# IoTSensorSchematic.net
KiCad netlist of a schematic drawn in EAGLE
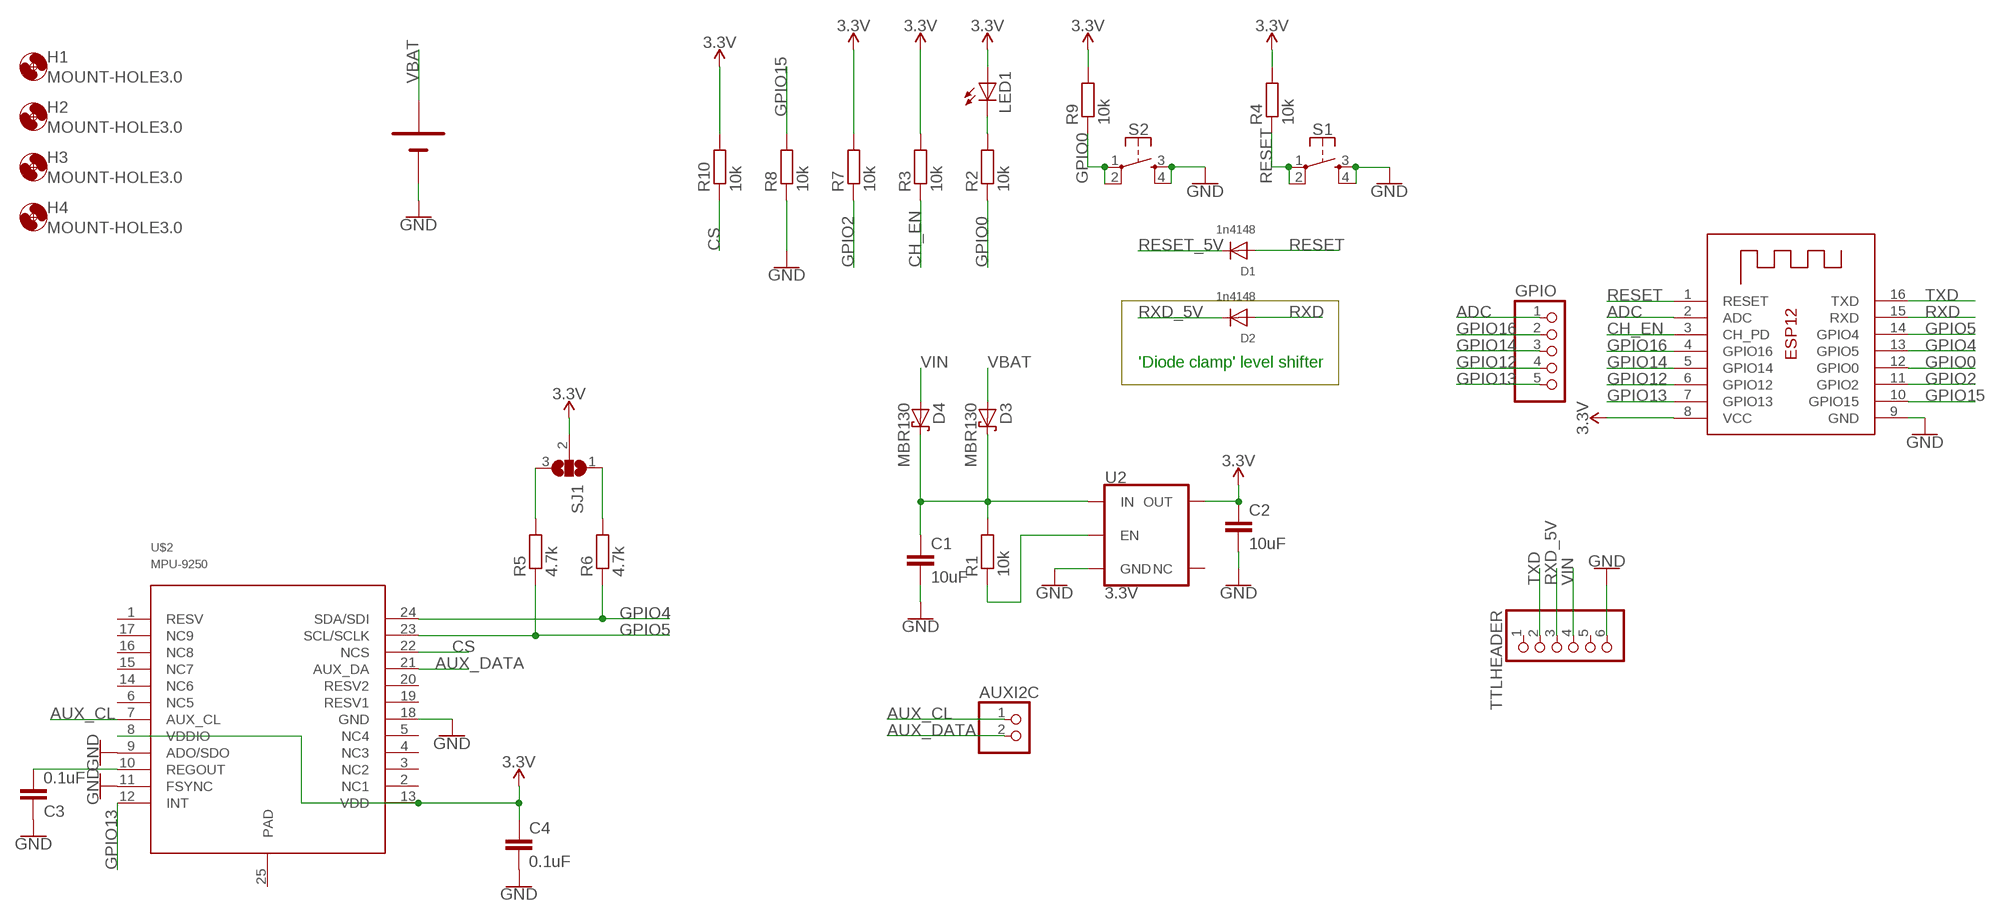
[diagram p0: schematic, sheet 1]

(export (version "E")
  (design (tool "Eeschema 10.0.6"))
  (components
    (comp (ref "AUXI2C")
      (value "PINHD-1X2")
      (footprint "eagle-import:1X02")
      (libsource (lib "eagle-import") (part "PINHD-1X2"))
    )
    (comp (ref "C1")
      (value "10uF")
      (footprint "eagle-import:C0805")
      (libsource (lib "eagle-import") (part "C-EUC0805"))
    )
    (comp (ref "C2")
      (value "10uF")
      (footprint "eagle-import:C0805")
      (libsource (lib "eagle-import") (part "C-EUC0805"))
    )
    (comp (ref "C3")
      (value "0.1uF")
      (footprint "eagle-import:C0805")
      (libsource (lib "eagle-import") (part "C-EUC0805"))
    )
    (comp (ref "C4")
      (value "0.1uF")
      (footprint "eagle-import:C0805")
      (libsource (lib "eagle-import") (part "C-EUC0805"))
    )
    (comp (ref "D1")
      (value "1n4148")
      (footprint "eagle-import:SMADIODE")
      (libsource (lib "eagle-import") (part "DIODESMA"))
    )
    (comp (ref "D2")
      (value "1n4148")
      (footprint "eagle-import:SMADIODE")
      (libsource (lib "eagle-import") (part "DIODESMA"))
    )
    (comp (ref "D3")
      (value "MBR130")
      (footprint "eagle-import:SMB")
      (libsource (lib "eagle-import") (part "MBRS130LT3"))
    )
    (comp (ref "D4")
      (value "MBR130")
      (footprint "eagle-import:SMB")
      (libsource (lib "eagle-import") (part "MBRS130LT3"))
    )
    (comp (ref "GPIO")
      (value "PINHD-1X5")
      (footprint "eagle-import:1X05")
      (libsource (lib "eagle-import") (part "PINHD-1X5"))
    )
    (comp (ref "H1")
      (value "MOUNT-HOLE3.0")
      (footprint "eagle-import:3,0")
      (libsource (lib "eagle-import") (part "MOUNT-HOLE3.0"))
    )
    (comp (ref "H2")
      (value "MOUNT-HOLE3.0")
      (footprint "eagle-import:3,0")
      (libsource (lib "eagle-import") (part "MOUNT-HOLE3.0"))
    )
    (comp (ref "H3")
      (value "MOUNT-HOLE3.0")
      (footprint "eagle-import:3,0")
      (libsource (lib "eagle-import") (part "MOUNT-HOLE3.0"))
    )
    (comp (ref "H4")
      (value "MOUNT-HOLE3.0")
      (footprint "eagle-import:3,0")
      (libsource (lib "eagle-import") (part "MOUNT-HOLE3.0"))
    )
    (comp (ref "LED1")
      (value "LEDCHIP-LED0805")
      (footprint "eagle-import:CHIP-LED0805")
      (libsource (lib "eagle-import") (part "LEDCHIP-LED0805"))
    )
    (comp (ref "R1")
      (value "10k")
      (footprint "eagle-import:R0805")
      (libsource (lib "eagle-import") (part "R-EU_R0805"))
    )
    (comp (ref "R2")
      (value "10k")
      (footprint "eagle-import:R0805")
      (libsource (lib "eagle-import") (part "R-EU_R0805"))
    )
    (comp (ref "R3")
      (value "10k")
      (footprint "eagle-import:R0805")
      (libsource (lib "eagle-import") (part "R-EU_R0805"))
    )
    (comp (ref "R4")
      (value "10k")
      (footprint "eagle-import:R0805")
      (libsource (lib "eagle-import") (part "R-EU_R0805"))
    )
    (comp (ref "R5")
      (value "4.7k")
      (footprint "eagle-import:R0805")
      (libsource (lib "eagle-import") (part "R-EU_R0805"))
    )
    (comp (ref "R6")
      (value "4.7k")
      (footprint "eagle-import:R0805")
      (libsource (lib "eagle-import") (part "R-EU_R0805"))
    )
    (comp (ref "R7")
      (value "10k")
      (footprint "eagle-import:R0805")
      (libsource (lib "eagle-import") (part "R-EU_R0805"))
    )
    (comp (ref "R8")
      (value "10k")
      (footprint "eagle-import:R0805")
      (libsource (lib "eagle-import") (part "R-EU_R0805"))
    )
    (comp (ref "R9")
      (value "10k")
      (footprint "eagle-import:R0805")
      (libsource (lib "eagle-import") (part "R-EU_R0805"))
    )
    (comp (ref "R10")
      (value "10k")
      (footprint "eagle-import:R0805")
      (libsource (lib "eagle-import") (part "R-EU_R0805"))
    )
    (comp (ref "S1")
      (value "MOMENTARY-SWITCH-SPST-2-SMD-5.2MM")
      (footprint "eagle-import:TACTILE_SWITCH_SMD_5.2MM")
      (libsource (lib "eagle-import") (part "MOMENTARY-SWITCH-SPST-2-SMD-5.2MM"))
    )
    (comp (ref "S2")
      (value "MOMENTARY-SWITCH-SPST-2-SMD-5.2MM")
      (footprint "eagle-import:TACTILE_SWITCH_SMD_5.2MM")
      (libsource (lib "eagle-import") (part "MOMENTARY-SWITCH-SPST-2-SMD-5.2MM"))
    )
    (comp (ref "SJ1")
      (value "SJ2W")
      (footprint "eagle-import:SJ_2")
      (libsource (lib "eagle-import") (part "SJ2W"))
    )
    (comp (ref "TTLHEADER")
      (value "PINHD-1X6")
      (footprint "eagle-import:1X06")
      (libsource (lib "eagle-import") (part "PINHD-1X6"))
    )
    (comp (ref "U$1")
      (value "SMTU_2450N")
      (footprint "eagle-import:SMTU_2450N")
      (libsource (lib "eagle-import") (part "SMTU_2450N"))
    )
    (comp (ref "U$2")
      (value "MPU-9250")
      (footprint "eagle-import:LEAD-QFN24")
      (libsource (lib "eagle-import") (part "MPU-9250"))
    )
    (comp (ref "U2")
      (value "3.3V")
      (footprint "eagle-import:SOT23-5")
      (libsource (lib "eagle-import") (part "V_REG_AP2112K-3.3V"))
    )
    (comp (ref "X1")
      (value "ESP-12")
      (footprint "eagle-import:ESP-12")
      (libsource (lib "eagle-import") (part "ESP-12"))
    )
  )
  (nets
    (net (code "1") (name "/ADC") (class "Default")
      (node (ref "GPIO") (pin "1") (pinfunction "1_1") (pintype "passive"))
      (node (ref "X1") (pin "2") (pinfunction "ADC_2") (pintype "passive"))
    )
    (net (code "2") (name "/AUX_CL") (class "Default")
      (node (ref "AUXI2C") (pin "1") (pinfunction "1_1") (pintype "passive"))
      (node (ref "U$2") (pin "7") (pinfunction "AUX_CL_7") (pintype "bidirectional"))
    )
    (net (code "3") (name "/AUX_DATA") (class "Default")
      (node (ref "AUXI2C") (pin "2") (pinfunction "2_2") (pintype "passive"))
      (node (ref "U$2") (pin "21") (pinfunction "AUX_DA_21") (pintype "bidirectional"))
    )
    (net (code "4") (name "/CH_EN") (class "Default")
      (node (ref "R3") (pin "1") (pinfunction "1_1") (pintype "passive"))
      (node (ref "X1") (pin "3") (pinfunction "CH_PD_3") (pintype "input"))
    )
    (net (code "5") (name "/CS") (class "Default")
      (node (ref "R10") (pin "1") (pinfunction "1_1") (pintype "passive"))
      (node (ref "U$2") (pin "22") (pinfunction "NCS_22") (pintype "bidirectional"))
    )
    (net (code "6") (name "/GPIO0") (class "Default")
      (node (ref "R2") (pin "1") (pinfunction "1_1") (pintype "passive"))
      (node (ref "R9") (pin "1") (pinfunction "1_1") (pintype "passive"))
      (node (ref "S2") (pin "1") (pinfunction "1_1") (pintype "passive"))
      (node (ref "S2") (pin "2") (pinfunction "2_2") (pintype "passive"))
      (node (ref "X1") (pin "12") (pinfunction "GPIO0_12") (pintype "bidirectional"))
    )
    (net (code "7") (name "/GPIO2") (class "Default")
      (node (ref "R7") (pin "1") (pinfunction "1_1") (pintype "passive"))
      (node (ref "X1") (pin "11") (pinfunction "GPIO2_11") (pintype "bidirectional"))
    )
    (net (code "8") (name "/GPIO4") (class "Default")
      (node (ref "R6") (pin "1") (pinfunction "1_1") (pintype "passive"))
      (node (ref "U$2") (pin "24") (pinfunction "SDA/SDI_24") (pintype "bidirectional"))
      (node (ref "X1") (pin "13") (pinfunction "GPIO5_13") (pintype "bidirectional"))
    )
    (net (code "9") (name "/GPIO5") (class "Default")
      (node (ref "R5") (pin "1") (pinfunction "1_1") (pintype "passive"))
      (node (ref "U$2") (pin "23") (pinfunction "SCL/SCLK_23") (pintype "bidirectional"))
      (node (ref "X1") (pin "14") (pinfunction "GPIO4_14") (pintype "bidirectional"))
    )
    (net (code "10") (name "/GPIO12") (class "Default")
      (node (ref "GPIO") (pin "4") (pinfunction "4_4") (pintype "passive"))
      (node (ref "X1") (pin "6") (pinfunction "GPIO12_6") (pintype "bidirectional"))
    )
    (net (code "11") (name "/GPIO13") (class "Default")
      (node (ref "GPIO") (pin "5") (pinfunction "5_5") (pintype "passive"))
      (node (ref "U$2") (pin "12") (pinfunction "INT_12") (pintype "bidirectional"))
      (node (ref "X1") (pin "7") (pinfunction "GPIO13_7") (pintype "bidirectional"))
    )
    (net (code "12") (name "/GPIO14") (class "Default")
      (node (ref "GPIO") (pin "3") (pinfunction "3_3") (pintype "passive"))
      (node (ref "X1") (pin "5") (pinfunction "GPIO14_5") (pintype "bidirectional"))
    )
    (net (code "13") (name "/GPIO15") (class "Default")
      (node (ref "R8") (pin "2") (pinfunction "2_2") (pintype "passive"))
      (node (ref "X1") (pin "10") (pinfunction "GPIO15_10") (pintype "bidirectional"))
    )
    (net (code "14") (name "/GPIO16") (class "Default")
      (node (ref "GPIO") (pin "2") (pinfunction "2_2") (pintype "passive"))
      (node (ref "X1") (pin "4") (pinfunction "GPIO16_4") (pintype "bidirectional"))
    )
    (net (code "15") (name "/RESET") (class "Default")
      (node (ref "D1") (pin "A") (pinfunction "A_A") (pintype "passive"))
      (node (ref "R4") (pin "1") (pinfunction "1_1") (pintype "passive"))
      (node (ref "S1") (pin "1") (pinfunction "1_1") (pintype "passive"))
      (node (ref "S1") (pin "2") (pinfunction "2_2") (pintype "passive"))
      (node (ref "X1") (pin "1") (pinfunction "RESET_1") (pintype "input"))
    )
    (net (code "16") (name "/RESET_5V") (class "Default")
      (node (ref "D1") (pin "C") (pinfunction "C_C") (pintype "passive"))
    )
    (net (code "17") (name "/RXD") (class "Default")
      (node (ref "D2") (pin "A") (pinfunction "A_A") (pintype "passive"))
      (node (ref "X1") (pin "15") (pinfunction "RXD_15") (pintype "input"))
    )
    (net (code "18") (name "/RXD_5V") (class "Default")
      (node (ref "D2") (pin "C") (pinfunction "C_C") (pintype "passive"))
      (node (ref "TTLHEADER") (pin "3") (pinfunction "3_3") (pintype "passive"))
    )
    (net (code "19") (name "/TXD") (class "Default")
      (node (ref "TTLHEADER") (pin "2") (pinfunction "2_2") (pintype "passive"))
      (node (ref "X1") (pin "16") (pinfunction "TXD_16") (pintype "output"))
    )
    (net (code "20") (name "/VBAT") (class "Default")
      (node (ref "D3") (pin "A") (pinfunction "A_A") (pintype "passive"))
      (node (ref "U$1") (pin "P$2") (pinfunction "P$2P_P$2") (pintype "bidirectional"))
    )
    (net (code "21") (name "/VIN") (class "Default")
      (node (ref "D4") (pin "A") (pinfunction "A_A") (pintype "passive"))
      (node (ref "TTLHEADER") (pin "4") (pinfunction "4_4") (pintype "passive"))
    )
    (net (code "22") (name "3.3V") (class "Default")
      (node (ref "C2") (pin "1") (pinfunction "1_1") (pintype "passive"))
      (node (ref "C4") (pin "1") (pinfunction "1_1") (pintype "passive"))
      (node (ref "LED1") (pin "A") (pinfunction "A_A") (pintype "passive"))
      (node (ref "R10") (pin "2") (pinfunction "2_2") (pintype "passive"))
      (node (ref "R3") (pin "2") (pinfunction "2_2") (pintype "passive"))
      (node (ref "R4") (pin "2") (pinfunction "2_2") (pintype "passive"))
      (node (ref "R7") (pin "2") (pinfunction "2_2") (pintype "passive"))
      (node (ref "R9") (pin "2") (pinfunction "2_2") (pintype "passive"))
      (node (ref "SJ1") (pin "2") (pinfunction "2_2") (pintype "passive"))
      (node (ref "U$2") (pin "13") (pinfunction "VDD_13") (pintype "bidirectional"))
      (node (ref "U$2") (pin "8") (pinfunction "VDDIO_8") (pintype "bidirectional"))
      (node (ref "U2") (pin "5") (pinfunction "OUT_5") (pintype "passive"))
      (node (ref "X1") (pin "8") (pinfunction "VCC_8") (pintype "power_in"))
    )
    (net (code "23") (name "GND") (class "Default")
      (node (ref "C1") (pin "2") (pinfunction "2_2") (pintype "passive"))
      (node (ref "C2") (pin "2") (pinfunction "2_2") (pintype "passive"))
      (node (ref "C3") (pin "1") (pinfunction "1_1") (pintype "passive"))
      (node (ref "C4") (pin "2") (pinfunction "2_2") (pintype "passive"))
      (node (ref "R8") (pin "1") (pinfunction "1_1") (pintype "passive"))
      (node (ref "S1") (pin "3") (pinfunction "3_3") (pintype "passive"))
      (node (ref "S1") (pin "4") (pinfunction "4_4") (pintype "passive"))
      (node (ref "S2") (pin "3") (pinfunction "3_3") (pintype "passive"))
      (node (ref "S2") (pin "4") (pinfunction "4_4") (pintype "passive"))
      (node (ref "TTLHEADER") (pin "6") (pinfunction "6_6") (pintype "passive"))
      (node (ref "U$1") (pin "P$1") (pinfunction "P$1N_P$1") (pintype "bidirectional"))
      (node (ref "U$2") (pin "11") (pinfunction "FSYNC_11") (pintype "bidirectional"))
      (node (ref "U$2") (pin "18") (pinfunction "GND_18") (pintype "bidirectional"))
      (node (ref "U$2") (pin "9") (pinfunction "ADO/SDO_9") (pintype "bidirectional"))
      (node (ref "U2") (pin "2") (pinfunction "GND_2") (pintype "input"))
      (node (ref "X1") (pin "9") (pinfunction "GND_9") (pintype "power_in"))
    )
    (net (code "24") (name "Net-(LED1-PadC)") (class "Default")
      (node (ref "LED1") (pin "C") (pinfunction "C_C") (pintype "passive"))
      (node (ref "R2") (pin "2") (pinfunction "2_2") (pintype "passive"))
    )
    (net (code "25") (name "Net-(R5-Pad2)") (class "Default")
      (node (ref "R5") (pin "2") (pinfunction "2_2") (pintype "passive"))
      (node (ref "SJ1") (pin "3") (pinfunction "3_3") (pintype "passive"))
    )
    (net (code "26") (name "Net-(R6-Pad2)") (class "Default")
      (node (ref "R6") (pin "2") (pinfunction "2_2") (pintype "passive"))
      (node (ref "SJ1") (pin "1") (pinfunction "1_1") (pintype "passive"))
    )
    (net (code "27") (name "Net-(U$2-REGOUT)") (class "Default")
      (node (ref "C3") (pin "2") (pinfunction "2_2") (pintype "passive"))
      (node (ref "U$2") (pin "10") (pinfunction "REGOUT_10") (pintype "bidirectional"))
    )
    (net (code "28") (name "Net-(U2-EN)") (class "Default")
      (node (ref "R1") (pin "1") (pinfunction "1_1") (pintype "passive"))
      (node (ref "U2") (pin "3") (pinfunction "EN_3") (pintype "input"))
    )
    (net (code "29") (name "Net-(U2-IN)") (class "Default")
      (node (ref "C1") (pin "1") (pinfunction "1_1") (pintype "passive"))
      (node (ref "D3") (pin "C") (pinfunction "C_C") (pintype "passive"))
      (node (ref "D4") (pin "C") (pinfunction "C_C") (pintype "passive"))
      (node (ref "R1") (pin "2") (pinfunction "2_2") (pintype "passive"))
      (node (ref "U2") (pin "1") (pinfunction "IN_1") (pintype "input"))
    )
    (net (code "30") (name "unconnected-(TTLHEADER-Pad1)") (class "Default")
      (node (ref "TTLHEADER") (pin "1") (pinfunction "1_1") (pintype "passive"))
    )
    (net (code "31") (name "unconnected-(TTLHEADER-Pad5)") (class "Default")
      (node (ref "TTLHEADER") (pin "5") (pinfunction "5_5") (pintype "passive"))
    )
    (net (code "32") (name "unconnected-(U$2-NC1-Pad2)") (class "Default")
      (node (ref "U$2") (pin "2") (pinfunction "NC1_2") (pintype "bidirectional"))
    )
    (net (code "33") (name "unconnected-(U$2-NC2-Pad3)") (class "Default")
      (node (ref "U$2") (pin "3") (pinfunction "NC2_3") (pintype "bidirectional"))
    )
    (net (code "34") (name "unconnected-(U$2-NC3-Pad4)") (class "Default")
      (node (ref "U$2") (pin "4") (pinfunction "NC3_4") (pintype "bidirectional"))
    )
    (net (code "35") (name "unconnected-(U$2-NC4-Pad5)") (class "Default")
      (node (ref "U$2") (pin "5") (pinfunction "NC4_5") (pintype "bidirectional"))
    )
    (net (code "36") (name "unconnected-(U$2-NC5-Pad6)") (class "Default")
      (node (ref "U$2") (pin "6") (pinfunction "NC5_6") (pintype "bidirectional"))
    )
    (net (code "37") (name "unconnected-(U$2-NC6-Pad14)") (class "Default")
      (node (ref "U$2") (pin "14") (pinfunction "NC6_14") (pintype "bidirectional"))
    )
    (net (code "38") (name "unconnected-(U$2-NC7-Pad15)") (class "Default")
      (node (ref "U$2") (pin "15") (pinfunction "NC7_15") (pintype "bidirectional"))
    )
    (net (code "39") (name "unconnected-(U$2-NC8-Pad16)") (class "Default")
      (node (ref "U$2") (pin "16") (pinfunction "NC8_16") (pintype "bidirectional"))
    )
    (net (code "40") (name "unconnected-(U$2-NC9-Pad17)") (class "Default")
      (node (ref "U$2") (pin "17") (pinfunction "NC9_17") (pintype "bidirectional"))
    )
    (net (code "41") (name "unconnected-(U$2-PAD-Pad25)") (class "Default")
      (node (ref "U$2") (pin "25") (pinfunction "PAD_25") (pintype "bidirectional"))
    )
    (net (code "42") (name "unconnected-(U$2-RESV-Pad1)") (class "Default")
      (node (ref "U$2") (pin "1") (pinfunction "RESV_1") (pintype "bidirectional"))
    )
    (net (code "43") (name "unconnected-(U$2-RESV1-Pad19)") (class "Default")
      (node (ref "U$2") (pin "19") (pinfunction "RESV1_19") (pintype "bidirectional"))
    )
    (net (code "44") (name "unconnected-(U$2-RESV2-Pad20)") (class "Default")
      (node (ref "U$2") (pin "20") (pinfunction "RESV2_20") (pintype "bidirectional"))
    )
    (net (code "45") (name "unconnected-(U2-NC-Pad4)") (class "Default")
      (node (ref "U2") (pin "4") (pinfunction "NC_4") (pintype "no_connect"))
    )
  )
)
